# TestBench_rev3.net
KiCad netlist of a schematic drawn in EAGLE
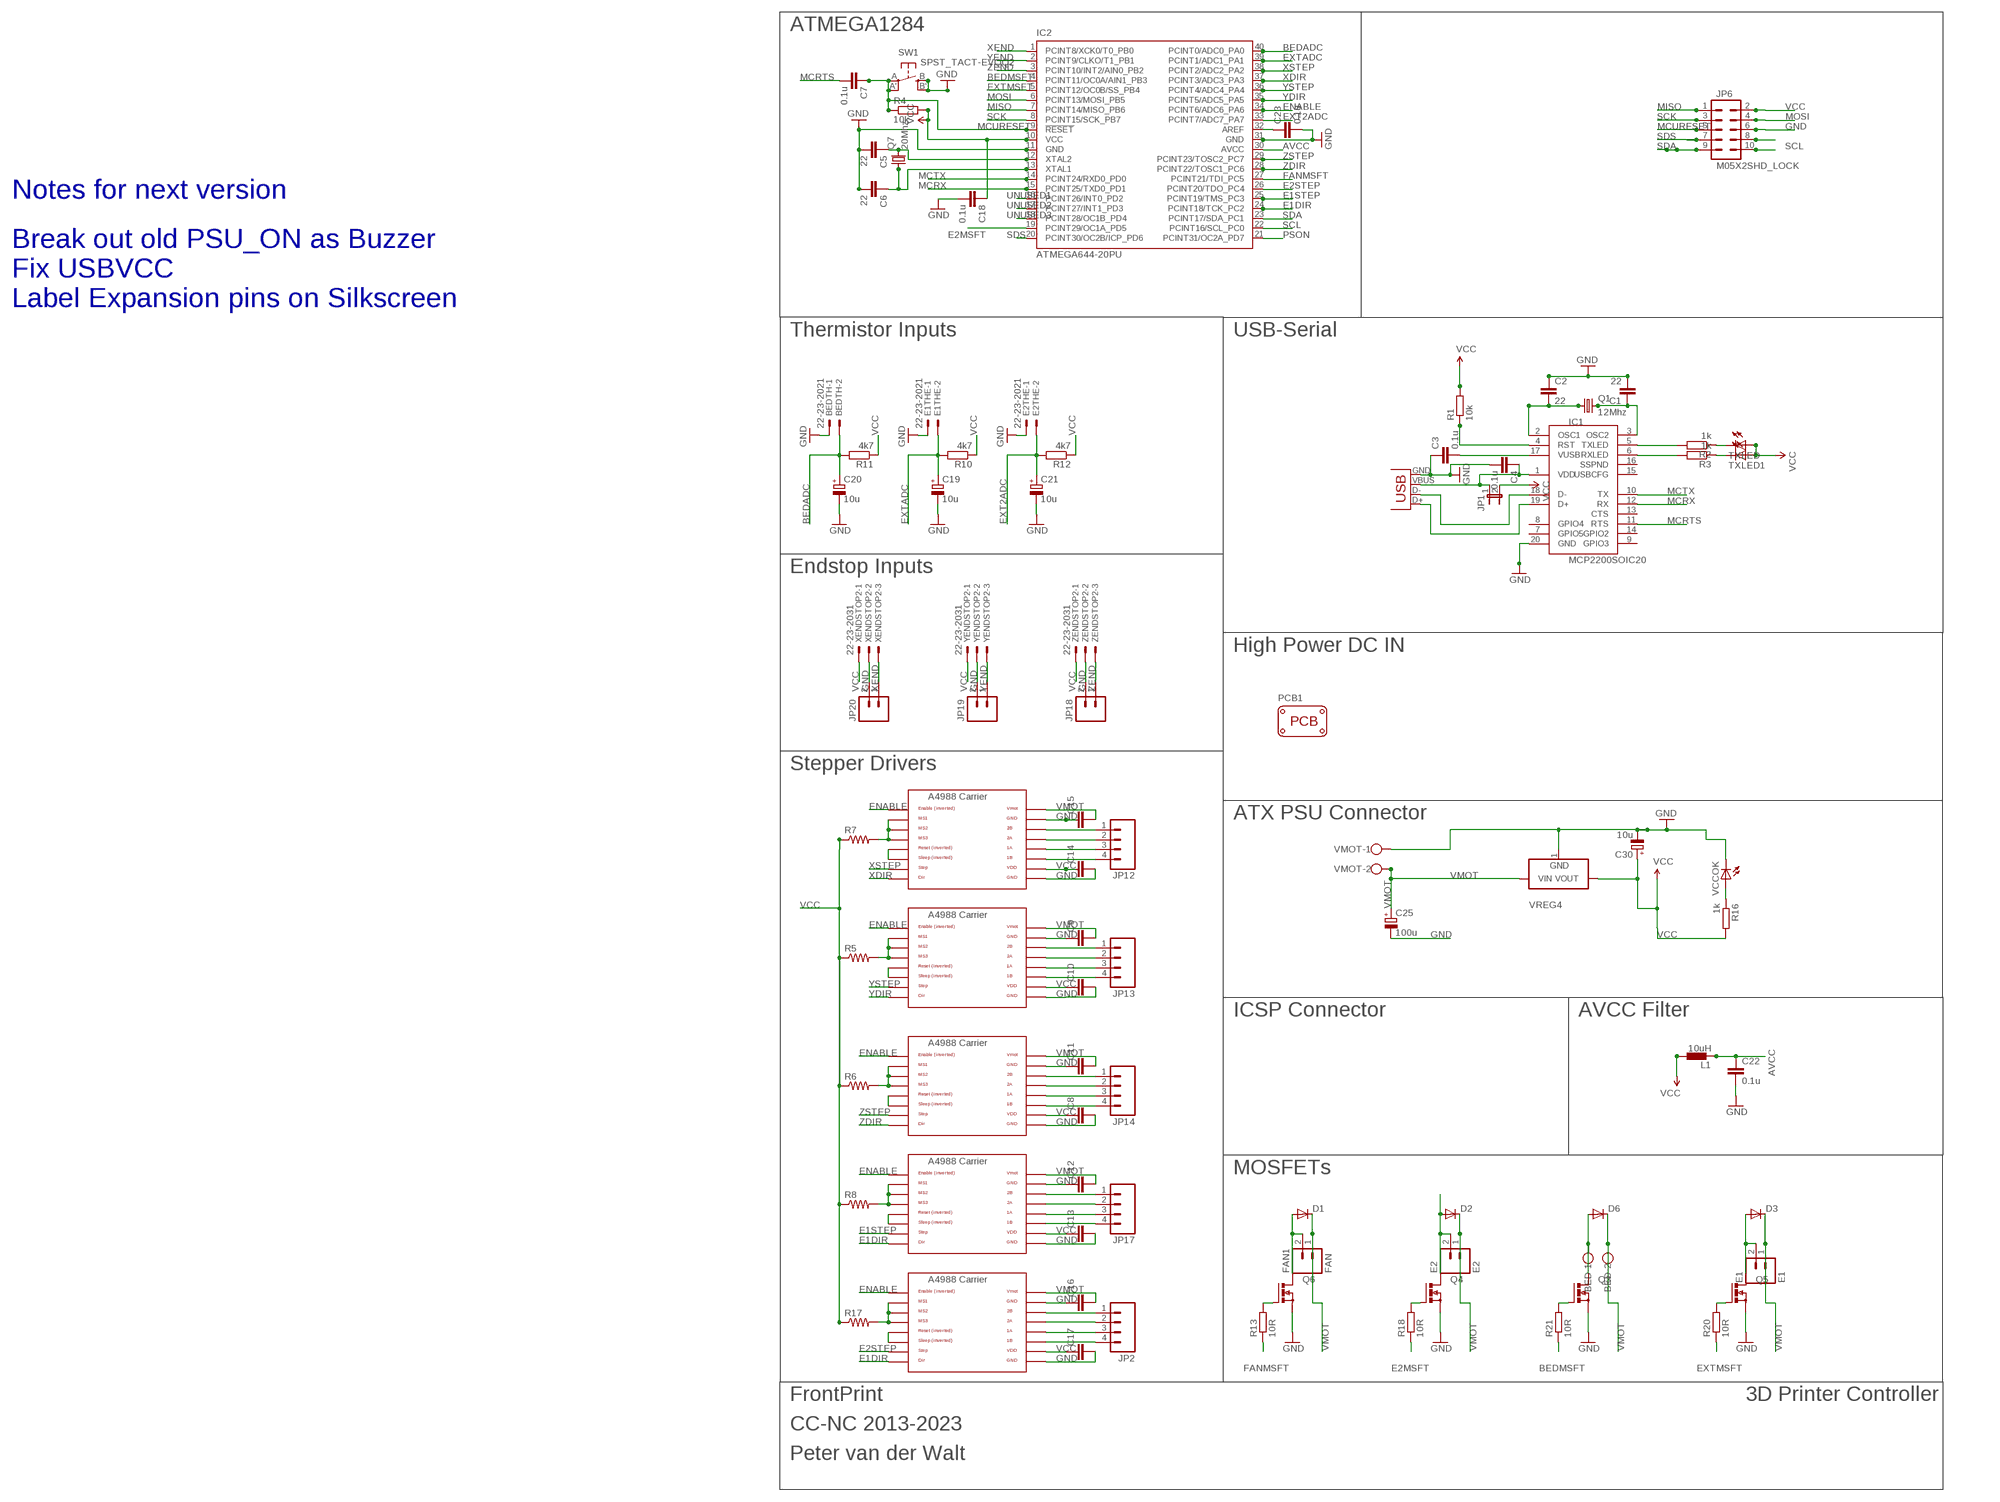
[diagram p0: schematic, sheet 1]

(export (version "E")
  (design (tool "Eeschema 10.0.6"))
  (components
    (comp (ref "BED")
      (value "W237-102")
      (footprint "eagle-import:W237-102")
      (fields (field (name "MPN") "237-102"))
      (libsource (lib "eagle-import") (part "W237-102"))
    )
    (comp (ref "BEDTH")
      (value "22-23-2021")
      (footprint "eagle-import:22-23-2021")
      (fields (field (name "MF") "MOLEX"))
      (libsource (lib "eagle-import") (part "22-23-2021"))
    )
    (comp (ref "C1")
      (value "22")
      (footprint "eagle-import:1206")
      (libsource (lib "eagle-import") (part "CAP1206"))
    )
    (comp (ref "C2")
      (value "22")
      (footprint "eagle-import:1206")
      (libsource (lib "eagle-import") (part "CAP1206"))
    )
    (comp (ref "C3")
      (value "0.1u")
      (footprint "eagle-import:1206")
      (libsource (lib "eagle-import") (part "CAP1206"))
    )
    (comp (ref "C4")
      (value "0.1u")
      (footprint "eagle-import:1206")
      (libsource (lib "eagle-import") (part "CAP1206"))
    )
    (comp (ref "C5")
      (value "22")
      (footprint "eagle-import:1206")
      (libsource (lib "eagle-import") (part "CAP1206"))
    )
    (comp (ref "C6")
      (value "22")
      (footprint "eagle-import:1206")
      (libsource (lib "eagle-import") (part "CAP1206"))
    )
    (comp (ref "C7")
      (value "0.1u")
      (footprint "eagle-import:1206")
      (libsource (lib "eagle-import") (part "CAP1206"))
    )
    (comp (ref "C8")
      (value "CAP1206")
      (footprint "eagle-import:1206")
      (libsource (lib "eagle-import") (part "CAP1206"))
    )
    (comp (ref "C9")
      (value "CAP1206")
      (footprint "eagle-import:1206")
      (libsource (lib "eagle-import") (part "CAP1206"))
    )
    (comp (ref "C10")
      (value "CAP1206")
      (footprint "eagle-import:1206")
      (libsource (lib "eagle-import") (part "CAP1206"))
    )
    (comp (ref "C11")
      (value "CAP1206")
      (footprint "eagle-import:1206")
      (libsource (lib "eagle-import") (part "CAP1206"))
    )
    (comp (ref "C12")
      (value "CAP1206")
      (footprint "eagle-import:1206")
      (libsource (lib "eagle-import") (part "CAP1206"))
    )
    (comp (ref "C13")
      (value "CAP1206")
      (footprint "eagle-import:1206")
      (libsource (lib "eagle-import") (part "CAP1206"))
    )
    (comp (ref "C14")
      (value "CAP1206")
      (footprint "eagle-import:1206")
      (libsource (lib "eagle-import") (part "CAP1206"))
    )
    (comp (ref "C15")
      (value "CAP1206")
      (footprint "eagle-import:1206")
      (libsource (lib "eagle-import") (part "CAP1206"))
    )
    (comp (ref "C16")
      (value "CAP1206")
      (footprint "eagle-import:1206")
      (libsource (lib "eagle-import") (part "CAP1206"))
    )
    (comp (ref "C17")
      (value "CAP1206")
      (footprint "eagle-import:1206")
      (libsource (lib "eagle-import") (part "CAP1206"))
    )
    (comp (ref "C18")
      (value "0.1u")
      (footprint "eagle-import:1206")
      (libsource (lib "eagle-import") (part "CAP1206"))
    )
    (comp (ref "C19")
      (value "10u")
      (footprint "eagle-import:E2,5-5")
      (libsource (lib "eagle-import") (part "CPOL-EUE2.5-5"))
    )
    (comp (ref "C20")
      (value "10u")
      (footprint "eagle-import:E2,5-5")
      (libsource (lib "eagle-import") (part "CPOL-EUE2.5-5"))
    )
    (comp (ref "C21")
      (value "10u")
      (footprint "eagle-import:E2,5-5")
      (libsource (lib "eagle-import") (part "CPOL-EUE2.5-5"))
    )
    (comp (ref "C22")
      (value "0.1u")
      (footprint "eagle-import:1206")
      (libsource (lib "eagle-import") (part "CAP1206"))
    )
    (comp (ref "C23")
      (value "0.1u")
      (footprint "eagle-import:1206")
      (libsource (lib "eagle-import") (part "CAP1206"))
    )
    (comp (ref "C25")
      (value "100u")
      (footprint "eagle-import:E5-8,5")
      (libsource (lib "eagle-import") (part "CPOL-EUE5-8.5"))
    )
    (comp (ref "C30")
      (value "10u")
      (footprint "eagle-import:E2-5")
      (libsource (lib "eagle-import") (part "CPOL-EUE2-5"))
    )
    (comp (ref "D1")
      (value "DIODESMA-ALT")
      (footprint "eagle-import:SMA-DIODE_ALT")
      (libsource (lib "eagle-import") (part "DIODESMA-ALT"))
    )
    (comp (ref "D2")
      (value "DIODESMA-ALT")
      (footprint "eagle-import:SMA-DIODE_ALT")
      (libsource (lib "eagle-import") (part "DIODESMA-ALT"))
    )
    (comp (ref "D3")
      (value "DIODESMA-ALT")
      (footprint "eagle-import:SMA-DIODE_ALT")
      (libsource (lib "eagle-import") (part "DIODESMA-ALT"))
    )
    (comp (ref "D6")
      (value "DIODESMA-ALT")
      (footprint "eagle-import:SMA-DIODE_ALT")
      (libsource (lib "eagle-import") (part "DIODESMA-ALT"))
    )
    (comp (ref "E1")
      (value "E1")
      (footprint "eagle-import:SCREWTERMINAL-3.5MM-2")
      (libsource (lib "eagle-import") (part "M023.5MM"))
    )
    (comp (ref "E1POL")
      (value "POLOLU_A4983CARRIER")
      (footprint "eagle-import:A4988BREAKOUT")
      (libsource (lib "eagle-import") (part "POLOLU_A4983CARRIER"))
    )
    (comp (ref "E1THE")
      (value "22-23-2021")
      (footprint "eagle-import:22-23-2021")
      (fields (field (name "MF") "MOLEX"))
      (libsource (lib "eagle-import") (part "22-23-2021"))
    )
    (comp (ref "E2")
      (value "E2")
      (footprint "eagle-import:SCREWTERMINAL-3.5MM-2")
      (libsource (lib "eagle-import") (part "M023.5MM"))
    )
    (comp (ref "E2POL")
      (value "POLOLU_A4983CARRIER")
      (footprint "eagle-import:A4988BREAKOUT")
      (libsource (lib "eagle-import") (part "POLOLU_A4983CARRIER"))
    )
    (comp (ref "E2THE")
      (value "22-23-2021")
      (footprint "eagle-import:22-23-2021")
      (fields (field (name "MF") "MOLEX"))
      (libsource (lib "eagle-import") (part "22-23-2021"))
    )
    (comp (ref "FAN1")
      (value "FAN")
      (footprint "eagle-import:SCREWTERMINAL-3.5MM-2")
      (libsource (lib "eagle-import") (part "M023.5MM"))
    )
    (comp (ref "IC1")
      (value "MCP2200SOIC20")
      (footprint "eagle-import:SOIC20")
      (libsource (lib "eagle-import") (part "MCP2200SOIC20"))
    )
    (comp (ref "IC2")
      (value "ATMEGA644-20PU")
      (footprint "eagle-import:DIL40")
      (libsource (lib "eagle-import") (part "ATMEGA644-PU20"))
    )
    (comp (ref "JP1")
      (value "JUMPER-2PTH_LOCK")
      (footprint "eagle-import:1X02_LOCK")
      (libsource (lib "eagle-import") (part "JUMPER-2PTH_LOCK"))
    )
    (comp (ref "JP2")
      (value "M04SCREW")
      (footprint "eagle-import:SCREWTERMINAL-3.5MM-4")
      (libsource (lib "eagle-import") (part "M04SCREW"))
    )
    (comp (ref "JP6")
      (value "M05X2SHD_LOCK")
      (footprint "eagle-import:2X5-SHROUDED_LOCK")
      (libsource (lib "eagle-import") (part "M05X2SHD_LOCK"))
    )
    (comp (ref "JP12")
      (value "M04SCREW")
      (footprint "eagle-import:SCREWTERMINAL-3.5MM-4")
      (libsource (lib "eagle-import") (part "M04SCREW"))
    )
    (comp (ref "JP13")
      (value "M04SCREW")
      (footprint "eagle-import:SCREWTERMINAL-3.5MM-4")
      (libsource (lib "eagle-import") (part "M04SCREW"))
    )
    (comp (ref "JP14")
      (value "M04SCREW")
      (footprint "eagle-import:SCREWTERMINAL-3.5MM-4")
      (libsource (lib "eagle-import") (part "M04SCREW"))
    )
    (comp (ref "JP17")
      (value "M04SCREW")
      (footprint "eagle-import:SCREWTERMINAL-3.5MM-4")
      (libsource (lib "eagle-import") (part "M04SCREW"))
    )
    (comp (ref "JP18")
      (value "M023.5MM")
      (footprint "eagle-import:SCREWTERMINAL-3.5MM-2")
      (libsource (lib "eagle-import") (part "M023.5MM"))
    )
    (comp (ref "JP19")
      (value "M023.5MM")
      (footprint "eagle-import:SCREWTERMINAL-3.5MM-2")
      (libsource (lib "eagle-import") (part "M023.5MM"))
    )
    (comp (ref "JP20")
      (value "M023.5MM")
      (footprint "eagle-import:SCREWTERMINAL-3.5MM-2")
      (libsource (lib "eagle-import") (part "M023.5MM"))
    )
    (comp (ref "L1")
      (value "10uH")
      (footprint "eagle-import:BL01RN1A")
      (libsource (lib "eagle-import") (part "BL01RN1A"))
    )
    (comp (ref "PCB1")
      (value "PCB_DP_SQUARE-10X10")
      (footprint "eagle-import:DP100100_V1")
      (libsource (lib "eagle-import") (part "PCB_DP_SQUARE-10X10"))
    )
    (comp (ref "Q1")
      (value "12Mhz")
      (footprint "eagle-import:HC49UP")
      (libsource (lib "eagle-import") (part "CRYSTALHC49UP"))
    )
    (comp (ref "Q3")
      (value "PMOSFET_NTO220BV")
      (footprint "eagle-import:TO220BV")
      (libsource (lib "eagle-import") (part "PMOSFET_NTO220BV"))
    )
    (comp (ref "Q4")
      (value "PMOSFET_NTO220BV")
      (footprint "eagle-import:TO220BV")
      (libsource (lib "eagle-import") (part "PMOSFET_NTO220BV"))
    )
    (comp (ref "Q5")
      (value "PMOSFET_NTO220BV")
      (footprint "eagle-import:TO220BV")
      (libsource (lib "eagle-import") (part "PMOSFET_NTO220BV"))
    )
    (comp (ref "Q6")
      (value "PMOSFET_NTO220BV")
      (footprint "eagle-import:TO220BV")
      (libsource (lib "eagle-import") (part "PMOSFET_NTO220BV"))
    )
    (comp (ref "Q7")
      (value "20Mhz")
      (footprint "eagle-import:HC49UP")
      (fields (field (name "OC_FARNELL") "unknown") (field (name "OC_NEWARK") "unknown"))
      (libsource (lib "eagle-import") (part "CRYSTALHC49UP"))
    )
    (comp (ref "R1")
      (value "10k")
      (footprint "eagle-import:M1206")
      (libsource (lib "eagle-import") (part "R-EU_M1206"))
    )
    (comp (ref "R2")
      (value "1k")
      (footprint "eagle-import:M1206")
      (libsource (lib "eagle-import") (part "R-EU_M1206"))
    )
    (comp (ref "R3")
      (value "1k")
      (footprint "eagle-import:M1206")
      (libsource (lib "eagle-import") (part "R-EU_M1206"))
    )
    (comp (ref "R4")
      (value "10k")
      (footprint "eagle-import:M1206")
      (libsource (lib "eagle-import") (part "R-EU_M1206"))
    )
    (comp (ref "R5")
      (value "RESISTOR1206")
      (footprint "eagle-import:1206")
      (libsource (lib "eagle-import") (part "RESISTOR1206"))
    )
    (comp (ref "R6")
      (value "RESISTOR1206")
      (footprint "eagle-import:1206")
      (libsource (lib "eagle-import") (part "RESISTOR1206"))
    )
    (comp (ref "R7")
      (value "RESISTOR1206")
      (footprint "eagle-import:1206")
      (libsource (lib "eagle-import") (part "RESISTOR1206"))
    )
    (comp (ref "R8")
      (value "RESISTOR1206")
      (footprint "eagle-import:1206")
      (libsource (lib "eagle-import") (part "RESISTOR1206"))
    )
    (comp (ref "R10")
      (value "4k7")
      (footprint "eagle-import:M1206")
      (libsource (lib "eagle-import") (part "R-EU_M1206"))
    )
    (comp (ref "R11")
      (value "4k7")
      (footprint "eagle-import:M1206")
      (libsource (lib "eagle-import") (part "R-EU_M1206"))
    )
    (comp (ref "R12")
      (value "4k7")
      (footprint "eagle-import:M1206")
      (libsource (lib "eagle-import") (part "R-EU_M1206"))
    )
    (comp (ref "R13")
      (value "10R")
      (footprint "eagle-import:M1206")
      (libsource (lib "eagle-import") (part "R-EU_M1206"))
    )
    (comp (ref "R16")
      (value "1k")
      (footprint "eagle-import:M1206")
      (libsource (lib "eagle-import") (part "R-EU_M1206"))
    )
    (comp (ref "R17")
      (value "RESISTOR1206")
      (footprint "eagle-import:1206")
      (libsource (lib "eagle-import") (part "RESISTOR1206"))
    )
    (comp (ref "R18")
      (value "10R")
      (footprint "eagle-import:M1206")
      (libsource (lib "eagle-import") (part "R-EU_M1206"))
    )
    (comp (ref "R20")
      (value "10R")
      (footprint "eagle-import:M1206")
      (libsource (lib "eagle-import") (part "R-EU_M1206"))
    )
    (comp (ref "R21")
      (value "10R")
      (footprint "eagle-import:M1206")
      (libsource (lib "eagle-import") (part "R-EU_M1206"))
    )
    (comp (ref "SW1")
      (value "SPST_TACT-EVQQ2")
      (footprint "eagle-import:EVQ-Q2")
      (libsource (lib "eagle-import") (part "SPST_TACT-EVQQ2"))
    )
    (comp (ref "TXLED")
      (value "LEDSMT1206")
      (footprint "eagle-import:1206")
      (libsource (lib "eagle-import") (part "LEDSMT1206"))
    )
    (comp (ref "TXLED1")
      (value "LEDSMT1206")
      (footprint "eagle-import:1206")
      (libsource (lib "eagle-import") (part "LEDSMT1206"))
    )
    (comp (ref "VCCOK")
      (value "LEDSMT1206")
      (footprint "eagle-import:1206")
      (libsource (lib "eagle-import") (part "LEDSMT1206"))
    )
    (comp (ref "VMOT")
      (value "W237-102")
      (footprint "eagle-import:W237-102")
      (fields
        (field (name "MPN") "237-102")
        (field (name "MPN_1") "237-102")
        (field (name "OC_FARNELL") "unknown")
        (field (name "OC_NEWARK") "70K9898")
      )
      (libsource (lib "eagle-import") (part "W237-102"))
    )
    (comp (ref "VREG4")
      (value "VREG_3PINS-DPAK")
      (footprint "eagle-import:DPAK")
      (libsource (lib "eagle-import") (part "VREG_3PINS-DPAK"))
    )
    (comp (ref "X1")
      (value "USBPTH")
      (footprint "eagle-import:USB-B-PTH")
      (libsource (lib "eagle-import") (part "USBPTH"))
    )
    (comp (ref "XENDSTOP2")
      (value "22-23-2031")
      (footprint "eagle-import:22-23-2031")
      (fields (field (name "MF") "MOLEX"))
      (libsource (lib "eagle-import") (part "22-23-2031"))
    )
    (comp (ref "XPOL")
      (value "POLOLU_A4983CARRIER")
      (footprint "eagle-import:A4988BREAKOUT")
      (libsource (lib "eagle-import") (part "POLOLU_A4983CARRIER"))
    )
    (comp (ref "YENDSTOP2")
      (value "22-23-2031")
      (footprint "eagle-import:22-23-2031")
      (fields (field (name "MF") "MOLEX"))
      (libsource (lib "eagle-import") (part "22-23-2031"))
    )
    (comp (ref "YPOL")
      (value "POLOLU_A4983CARRIER")
      (footprint "eagle-import:A4988BREAKOUT")
      (libsource (lib "eagle-import") (part "POLOLU_A4983CARRIER"))
    )
    (comp (ref "ZENDSTOP2")
      (value "22-23-2031")
      (footprint "eagle-import:22-23-2031")
      (fields (field (name "MF") "MOLEX"))
      (libsource (lib "eagle-import") (part "22-23-2031"))
    )
    (comp (ref "ZPOL")
      (value "POLOLU_A4983CARRIER")
      (footprint "eagle-import:A4988BREAKOUT")
      (libsource (lib "eagle-import") (part "POLOLU_A4983CARRIER"))
    )
  )
  (nets
    (net (code "1") (name "/AVCC") (class "Default")
      (node (ref "C22") (pin "1") (pinfunction "1_1") (pintype "passive"))
      (node (ref "IC2") (pin "30") (pinfunction "AVCC_30") (pintype "power_in"))
      (node (ref "L1") (pin "1") (pinfunction "1_1") (pintype "passive"))
    )
    (net (code "2") (name "/BEDADC") (class "Default")
      (node (ref "BEDTH") (pin "2") (pinfunction "S_2") (pintype "passive"))
      (node (ref "C20") (pin "+") (pinfunction "+_+") (pintype "passive"))
      (node (ref "IC2") (pin "40") (pinfunction "PCINT0/ADC0_PA0_40") (pintype "bidirectional"))
      (node (ref "R11") (pin "2") (pinfunction "2_2") (pintype "passive"))
    )
    (net (code "3") (name "/BEDMSFT") (class "Default")
      (node (ref "IC2") (pin "4") (pinfunction "PCINT11/OC0A/AIN1_PB3_4") (pintype "bidirectional"))
      (node (ref "R21") (pin "1") (pinfunction "1_1") (pintype "passive"))
    )
    (net (code "4") (name "/E1DIR") (class "Default")
      (node (ref "E1POL") (pin "DIR") (pinfunction "DIR_DIR") (pintype "input"))
      (node (ref "E2POL") (pin "DIR") (pinfunction "DIR_DIR") (pintype "input"))
      (node (ref "IC2") (pin "24") (pinfunction "PCINT18/TCK_PC2_24") (pintype "bidirectional"))
    )
    (net (code "5") (name "/E1STEP") (class "Default")
      (node (ref "E1POL") (pin "STEP") (pinfunction "STEP_STEP") (pintype "input"))
      (node (ref "IC2") (pin "25") (pinfunction "PCINT19/TMS_PC3_25") (pintype "bidirectional"))
    )
    (net (code "6") (name "/E2MSFT") (class "Default")
      (node (ref "IC2") (pin "19") (pinfunction "PCINT29/OC1A_PD5_19") (pintype "bidirectional"))
      (node (ref "R18") (pin "1") (pinfunction "1_1") (pintype "passive"))
    )
    (net (code "7") (name "/E2STEP") (class "Default")
      (node (ref "E2POL") (pin "STEP") (pinfunction "STEP_STEP") (pintype "input"))
      (node (ref "IC2") (pin "26") (pinfunction "PCINT20/TDO_PC4_26") (pintype "bidirectional"))
    )
    (net (code "8") (name "/ENABLE") (class "Default")
      (node (ref "E1POL") (pin "EN") (pinfunction "EN_EN") (pintype "input"))
      (node (ref "E2POL") (pin "EN") (pinfunction "EN_EN") (pintype "input"))
      (node (ref "IC2") (pin "34") (pinfunction "PCINT6/ADC6_PA6_34") (pintype "bidirectional"))
      (node (ref "XPOL") (pin "EN") (pinfunction "EN_EN") (pintype "input"))
      (node (ref "YPOL") (pin "EN") (pinfunction "EN_EN") (pintype "input"))
      (node (ref "ZPOL") (pin "EN") (pinfunction "EN_EN") (pintype "input"))
    )
    (net (code "9") (name "/EXT2ADC") (class "Default")
      (node (ref "C21") (pin "+") (pinfunction "+_+") (pintype "passive"))
      (node (ref "E2THE") (pin "2") (pinfunction "S_2") (pintype "passive"))
      (node (ref "IC2") (pin "33") (pinfunction "PCINT7/ADC7_PA7_33") (pintype "bidirectional"))
      (node (ref "R12") (pin "2") (pinfunction "2_2") (pintype "passive"))
    )
    (net (code "10") (name "/EXTADC") (class "Default")
      (node (ref "C19") (pin "+") (pinfunction "+_+") (pintype "passive"))
      (node (ref "E1THE") (pin "2") (pinfunction "S_2") (pintype "passive"))
      (node (ref "IC2") (pin "39") (pinfunction "PCINT1/ADC1_PA1_39") (pintype "bidirectional"))
      (node (ref "R10") (pin "2") (pinfunction "2_2") (pintype "passive"))
    )
    (net (code "11") (name "/EXTMSFT") (class "Default")
      (node (ref "IC2") (pin "5") (pinfunction "PCINT12/OC0B/SS_PB4_5") (pintype "bidirectional"))
      (node (ref "R20") (pin "1") (pinfunction "1_1") (pintype "passive"))
    )
    (net (code "12") (name "/FANMSFT") (class "Default")
      (node (ref "IC2") (pin "27") (pinfunction "PCINT21/TDI_PC5_27") (pintype "bidirectional"))
      (node (ref "R13") (pin "1") (pinfunction "1_1") (pintype "passive"))
    )
    (net (code "13") (name "/MCRTS") (class "Default")
      (node (ref "C7") (pin "2") (pinfunction "2_2") (pintype "passive"))
      (node (ref "IC1") (pin "11") (pinfunction "RTS_11") (pintype "bidirectional"))
    )
    (net (code "14") (name "/MCRX") (class "Default")
      (node (ref "IC1") (pin "12") (pinfunction "RX_12") (pintype "bidirectional"))
      (node (ref "IC2") (pin "15") (pinfunction "PCINT25/TXD0_PD1_15") (pintype "bidirectional"))
    )
    (net (code "15") (name "/MCTX") (class "Default")
      (node (ref "IC1") (pin "10") (pinfunction "TX_10") (pintype "bidirectional"))
      (node (ref "IC2") (pin "14") (pinfunction "PCINT24/RXD0_PD0_14") (pintype "bidirectional"))
    )
    (net (code "16") (name "/MCURESET") (class "Default")
      (node (ref "C7") (pin "1") (pinfunction "1_1") (pintype "passive"))
      (node (ref "IC2") (pin "9") (pinfunction "~{RESET}_9") (pintype "input"))
      (node (ref "JP6") (pin "5") (pinfunction "5_5") (pintype "passive"))
      (node (ref "R4") (pin "1") (pinfunction "1_1") (pintype "passive"))
      (node (ref "SW1") (pin "A") (pinfunction "P_A") (pintype "passive"))
      (node (ref "SW1") (pin "A'") (pinfunction "P1_A'") (pintype "passive"))
    )
    (net (code "17") (name "/MISO") (class "Default")
      (node (ref "IC2") (pin "7") (pinfunction "PCINT14/MISO_PB6_7") (pintype "bidirectional"))
      (node (ref "JP6") (pin "1") (pinfunction "1_1") (pintype "passive"))
    )
    (net (code "18") (name "/MOSI") (class "Default")
      (node (ref "IC2") (pin "6") (pinfunction "PCINT13/MOSI_PB5_6") (pintype "bidirectional"))
      (node (ref "JP6") (pin "4") (pinfunction "4_4") (pintype "passive"))
    )
    (net (code "19") (name "/PSON") (class "Default")
      (node (ref "IC2") (pin "21") (pinfunction "PCINT31/OC2A_PD7_21") (pintype "bidirectional"))
    )
    (net (code "20") (name "/SCK") (class "Default")
      (node (ref "IC2") (pin "8") (pinfunction "PCINT15/SCK_PB7_8") (pintype "bidirectional"))
      (node (ref "JP6") (pin "3") (pinfunction "3_3") (pintype "passive"))
    )
    (net (code "21") (name "/SCL") (class "Default")
      (node (ref "IC2") (pin "22") (pinfunction "PCINT16/SCL_PC0_22") (pintype "bidirectional"))
      (node (ref "JP6") (pin "10") (pinfunction "10_10") (pintype "passive"))
    )
    (net (code "22") (name "/SDA") (class "Default")
      (node (ref "IC2") (pin "23") (pinfunction "PCINT17/SDA_PC1_23") (pintype "bidirectional"))
      (node (ref "JP6") (pin "9") (pinfunction "9_9") (pintype "passive"))
    )
    (net (code "23") (name "/SDS") (class "Default")
      (node (ref "IC2") (pin "20") (pinfunction "PCINT30/OC2B/ICP_PD6_20") (pintype "bidirectional"))
      (node (ref "JP6") (pin "7") (pinfunction "7_7") (pintype "passive"))
    )
    (net (code "24") (name "/UNUSED1") (class "Default")
      (node (ref "IC2") (pin "16") (pinfunction "PCINT26/INT0_PD2_16") (pintype "bidirectional"))
    )
    (net (code "25") (name "/UNUSED2") (class "Default")
      (node (ref "IC2") (pin "17") (pinfunction "PCINT27/INT1_PD3_17") (pintype "bidirectional"))
    )
    (net (code "26") (name "/UNUSED3") (class "Default")
      (node (ref "IC2") (pin "18") (pinfunction "PCINT28/OC1B_PD4_18") (pintype "bidirectional"))
    )
    (net (code "27") (name "/VMOT") (class "Default")
      (node (ref "BED") (pin "2") (pinfunction "KL_2") (pintype "passive"))
      (node (ref "C11") (pin "2") (pinfunction "2_2") (pintype "passive"))
      (node (ref "C12") (pin "2") (pinfunction "2_2") (pintype "passive"))
      (node (ref "C15") (pin "2") (pinfunction "2_2") (pintype "passive"))
      (node (ref "C16") (pin "2") (pinfunction "2_2") (pintype "passive"))
      (node (ref "C25") (pin "+") (pinfunction "+_+") (pintype "passive"))
      (node (ref "C9") (pin "2") (pinfunction "2_2") (pintype "passive"))
      (node (ref "D1") (pin "C") (pinfunction "C_C") (pintype "passive"))
      (node (ref "D2") (pin "C") (pinfunction "C_C") (pintype "passive"))
      (node (ref "D3") (pin "C") (pinfunction "C_C") (pintype "passive"))
      (node (ref "D6") (pin "C") (pinfunction "C_C") (pintype "passive"))
      (node (ref "E1") (pin "1") (pinfunction "1_1") (pintype "passive"))
      (node (ref "E1POL") (pin "VMOT") (pinfunction "VMOT_VMOT") (pintype "power_in"))
      (node (ref "E2") (pin "1") (pinfunction "1_1") (pintype "passive"))
      (node (ref "E2POL") (pin "VMOT") (pinfunction "VMOT_VMOT") (pintype "power_in"))
      (node (ref "FAN1") (pin "1") (pinfunction "1_1") (pintype "passive"))
      (node (ref "VMOT") (pin "2") (pinfunction "KL_2") (pintype "passive"))
      (node (ref "VREG4") (pin "3") (pinfunction "VIN_3") (pintype "bidirectional"))
      (node (ref "XPOL") (pin "VMOT") (pinfunction "VMOT_VMOT") (pintype "power_in"))
      (node (ref "YPOL") (pin "VMOT") (pinfunction "VMOT_VMOT") (pintype "power_in"))
      (node (ref "ZPOL") (pin "VMOT") (pinfunction "VMOT_VMOT") (pintype "power_in"))
    )
    (net (code "28") (name "/XDIR") (class "Default")
      (node (ref "IC2") (pin "37") (pinfunction "PCINT3/ADC3_PA3_37") (pintype "bidirectional"))
      (node (ref "XPOL") (pin "DIR") (pinfunction "DIR_DIR") (pintype "input"))
    )
    (net (code "29") (name "/XEND") (class "Default")
      (node (ref "IC2") (pin "1") (pinfunction "PCINT8/XCK0/T0_PB0_1") (pintype "bidirectional"))
      (node (ref "JP20") (pin "1") (pinfunction "1_1") (pintype "passive"))
      (node (ref "XENDSTOP2") (pin "3") (pinfunction "S_3") (pintype "passive"))
    )
    (net (code "30") (name "/XSTEP") (class "Default")
      (node (ref "IC2") (pin "38") (pinfunction "PCINT2/ADC2_PA2_38") (pintype "bidirectional"))
      (node (ref "XPOL") (pin "STEP") (pinfunction "STEP_STEP") (pintype "input"))
    )
    (net (code "31") (name "/YDIR") (class "Default")
      (node (ref "IC2") (pin "35") (pinfunction "PCINT5/ADC5_PA5_35") (pintype "bidirectional"))
      (node (ref "YPOL") (pin "DIR") (pinfunction "DIR_DIR") (pintype "input"))
    )
    (net (code "32") (name "/YEND") (class "Default")
      (node (ref "IC2") (pin "2") (pinfunction "PCINT9/CLKO/T1_PB1_2") (pintype "bidirectional"))
      (node (ref "JP19") (pin "1") (pinfunction "1_1") (pintype "passive"))
      (node (ref "YENDSTOP2") (pin "3") (pinfunction "S_3") (pintype "passive"))
    )
    (net (code "33") (name "/YSTEP") (class "Default")
      (node (ref "IC2") (pin "36") (pinfunction "PCINT4/ADC4_PA4_36") (pintype "bidirectional"))
      (node (ref "YPOL") (pin "STEP") (pinfunction "STEP_STEP") (pintype "input"))
    )
    (net (code "34") (name "/ZDIR") (class "Default")
      (node (ref "IC2") (pin "28") (pinfunction "PCINT22/TOSC1_PC6_28") (pintype "bidirectional"))
      (node (ref "ZPOL") (pin "DIR") (pinfunction "DIR_DIR") (pintype "input"))
    )
    (net (code "35") (name "/ZEND") (class "Default")
      (node (ref "IC2") (pin "3") (pinfunction "PCINT10/INT2/AIN0_PB2_3") (pintype "bidirectional"))
      (node (ref "JP18") (pin "1") (pinfunction "1_1") (pintype "passive"))
      (node (ref "ZENDSTOP2") (pin "3") (pinfunction "S_3") (pintype "passive"))
    )
    (net (code "36") (name "/ZSTEP") (class "Default")
      (node (ref "IC2") (pin "29") (pinfunction "PCINT23/TOSC2_PC7_29") (pintype "bidirectional"))
      (node (ref "ZPOL") (pin "STEP") (pinfunction "STEP_STEP") (pintype "input"))
    )
    (net (code "37") (name "GND") (class "Default")
      (node (ref "BEDTH") (pin "1") (pinfunction "S_1") (pintype "passive"))
      (node (ref "C1") (pin "2") (pinfunction "2_2") (pintype "passive"))
      (node (ref "C10") (pin "2") (pinfunction "2_2") (pintype "passive"))
      (node (ref "C11") (pin "1") (pinfunction "1_1") (pintype "passive"))
      (node (ref "C12") (pin "1") (pinfunction "1_1") (pintype "passive"))
      (node (ref "C13") (pin "2") (pinfunction "2_2") (pintype "passive"))
      (node (ref "C14") (pin "2") (pinfunction "2_2") (pintype "passive"))
      (node (ref "C15") (pin "1") (pinfunction "1_1") (pintype "passive"))
      (node (ref "C16") (pin "1") (pinfunction "1_1") (pintype "passive"))
      (node (ref "C17") (pin "2") (pinfunction "2_2") (pintype "passive"))
      (node (ref "C18") (pin "2") (pinfunction "2_2") (pintype "passive"))
      (node (ref "C19") (pin "-") (pinfunction "-_-") (pintype "passive"))
      (node (ref "C2") (pin "1") (pinfunction "1_1") (pintype "passive"))
      (node (ref "C20") (pin "-") (pinfunction "-_-") (pintype "passive"))
      (node (ref "C21") (pin "-") (pinfunction "-_-") (pintype "passive"))
      (node (ref "C22") (pin "2") (pinfunction "2_2") (pintype "passive"))
      (node (ref "C23") (pin "2") (pinfunction "2_2") (pintype "passive"))
      (node (ref "C25") (pin "-") (pinfunction "-_-") (pintype "passive"))
      (node (ref "C3") (pin "1") (pinfunction "1_1") (pintype "passive"))
      (node (ref "C30") (pin "-") (pinfunction "-_-") (pintype "passive"))
      (node (ref "C4") (pin "2") (pinfunction "2_2") (pintype "passive"))
      (node (ref "C5") (pin "2") (pinfunction "2_2") (pintype "passive"))
      (node (ref "C6") (pin "2") (pinfunction "2_2") (pintype "passive"))
      (node (ref "C8") (pin "2") (pinfunction "2_2") (pintype "passive"))
      (node (ref "C9") (pin "1") (pinfunction "1_1") (pintype "passive"))
      (node (ref "E1POL") (pin "GND") (pinfunction "GND_GND") (pintype "power_in"))
      (node (ref "E1POL") (pin "GND@0") (pinfunction "GND_GND@0") (pintype "power_in"))
      (node (ref "E1THE") (pin "1") (pinfunction "S_1") (pintype "passive"))
      (node (ref "E2POL") (pin "GND") (pinfunction "GND_GND") (pintype "power_in"))
      (node (ref "E2POL") (pin "GND@0") (pinfunction "GND_GND@0") (pintype "power_in"))
      (node (ref "E2THE") (pin "1") (pinfunction "S_1") (pintype "passive"))
      (node (ref "IC1") (pin "20") (pinfunction "GND_20") (pintype "bidirectional"))
      (node (ref "IC2") (pin "11") (pinfunction "GND_11") (pintype "power_in"))
      (node (ref "IC2") (pin "31") (pinfunction "GND_31") (pintype "power_in"))
      (node (ref "JP18") (pin "2") (pinfunction "2_2") (pintype "passive"))
      (node (ref "JP19") (pin "2") (pinfunction "2_2") (pintype "passive"))
      (node (ref "JP20") (pin "2") (pinfunction "2_2") (pintype "passive"))
      (node (ref "JP6") (pin "6") (pinfunction "6_6") (pintype "passive"))
      (node (ref "Q3") (pin "S") (pinfunction "S_S") (pintype "passive"))
      (node (ref "Q4") (pin "S") (pinfunction "S_S") (pintype "passive"))
      (node (ref "Q5") (pin "S") (pinfunction "S_S") (pintype "passive"))
      (node (ref "Q6") (pin "S") (pinfunction "S_S") (pintype "passive"))
      (node (ref "SW1") (pin "B") (pinfunction "S_B") (pintype "passive"))
      (node (ref "SW1") (pin "B'") (pinfunction "S1_B'") (pintype "passive"))
      (node (ref "VCCOK") (pin "C") (pinfunction "C_C") (pintype "passive"))
      (node (ref "VMOT") (pin "1") (pinfunction "KL_1") (pintype "passive"))
      (node (ref "VREG4") (pin "1") (pinfunction "GND_1") (pintype "bidirectional"))
      (node (ref "X1") (pin "GND") (pinfunction "GND_GND") (pintype "bidirectional"))
      (node (ref "XENDSTOP2") (pin "2") (pinfunction "S_2") (pintype "passive"))
      (node (ref "XPOL") (pin "GND") (pinfunction "GND_GND") (pintype "power_in"))
      (node (ref "XPOL") (pin "GND@0") (pinfunction "GND_GND@0") (pintype "power_in"))
      (node (ref "YENDSTOP2") (pin "2") (pinfunction "S_2") (pintype "passive"))
      (node (ref "YPOL") (pin "GND") (pinfunction "GND_GND") (pintype "power_in"))
      (node (ref "YPOL") (pin "GND@0") (pinfunction "GND_GND@0") (pintype "power_in"))
      (node (ref "ZENDSTOP2") (pin "2") (pinfunction "S_2") (pintype "passive"))
      (node (ref "ZPOL") (pin "GND") (pinfunction "GND_GND") (pintype "power_in"))
      (node (ref "ZPOL") (pin "GND@0") (pinfunction "GND_GND@0") (pintype "power_in"))
    )
    (net (code "38") (name "Net-(BEDA-KL)") (class "Default")
      (node (ref "BED") (pin "1") (pinfunction "KL_1") (pintype "passive"))
      (node (ref "D6") (pin "A") (pinfunction "A_A") (pintype "passive"))
      (node (ref "Q3") (pin "D") (pinfunction "D_D") (pintype "passive"))
    )
    (net (code "39") (name "Net-(D1-PadA)") (class "Default")
      (node (ref "D1") (pin "A") (pinfunction "A_A") (pintype "passive"))
      (node (ref "FAN1") (pin "2") (pinfunction "2_2") (pintype "passive"))
      (node (ref "Q6") (pin "D") (pinfunction "D_D") (pintype "passive"))
    )
    (net (code "40") (name "Net-(D2-PadA)") (class "Default")
      (node (ref "D2") (pin "A") (pinfunction "A_A") (pintype "passive"))
      (node (ref "E2") (pin "2") (pinfunction "2_2") (pintype "passive"))
      (node (ref "Q4") (pin "D") (pinfunction "D_D") (pintype "passive"))
    )
    (net (code "41") (name "Net-(D3-PadA)") (class "Default")
      (node (ref "D3") (pin "A") (pinfunction "A_A") (pintype "passive"))
      (node (ref "E1") (pin "2") (pinfunction "2_2") (pintype "passive"))
      (node (ref "Q5") (pin "D") (pinfunction "D_D") (pintype "passive"))
    )
    (net (code "42") (name "Net-(E1POL-Pad1A)") (class "Default")
      (node (ref "E1POL") (pin "1A") (pinfunction "1A_1A") (pintype "output"))
      (node (ref "JP17") (pin "3") (pinfunction "3_3") (pintype "passive"))
    )
    (net (code "43") (name "Net-(E1POL-Pad1B)") (class "Default")
      (node (ref "E1POL") (pin "1B") (pinfunction "1B_1B") (pintype "output"))
      (node (ref "JP17") (pin "4") (pinfunction "4_4") (pintype "passive"))
    )
    (net (code "44") (name "Net-(E1POL-Pad2A)") (class "Default")
      (node (ref "E1POL") (pin "2A") (pinfunction "2A_2A") (pintype "output"))
      (node (ref "JP17") (pin "2") (pinfunction "2_2") (pintype "passive"))
    )
    (net (code "45") (name "Net-(E1POL-Pad2B)") (class "Default")
      (node (ref "E1POL") (pin "2B") (pinfunction "2B_2B") (pintype "output"))
      (node (ref "JP17") (pin "1") (pinfunction "1_1") (pintype "passive"))
    )
    (net (code "46") (name "Net-(E1POL-PadMS1)") (class "Default")
      (node (ref "E1POL") (pin "MS1") (pinfunction "MS1_MS1") (pintype "input"))
      (node (ref "E1POL") (pin "MS2") (pinfunction "MS2_MS2") (pintype "input"))
      (node (ref "E1POL") (pin "MS3") (pinfunction "MS3_MS3") (pintype "input"))
      (node (ref "R8") (pin "2") (pinfunction "2_2") (pintype "passive"))
    )
    (net (code "47") (name "Net-(E1POL-SLEEP)") (class "Default")
      (node (ref "E1POL") (pin "RST") (pinfunction "RST_RST") (pintype "input"))
      (node (ref "E1POL") (pin "SLP") (pinfunction "SLEEP_SLP") (pintype "input"))
    )
    (net (code "48") (name "Net-(E2POL-Pad1A)") (class "Default")
      (node (ref "E2POL") (pin "1A") (pinfunction "1A_1A") (pintype "output"))
      (node (ref "JP2") (pin "3") (pinfunction "3_3") (pintype "passive"))
    )
    (net (code "49") (name "Net-(E2POL-Pad1B)") (class "Default")
      (node (ref "E2POL") (pin "1B") (pinfunction "1B_1B") (pintype "output"))
      (node (ref "JP2") (pin "4") (pinfunction "4_4") (pintype "passive"))
    )
    (net (code "50") (name "Net-(E2POL-Pad2A)") (class "Default")
      (node (ref "E2POL") (pin "2A") (pinfunction "2A_2A") (pintype "output"))
      (node (ref "JP2") (pin "2") (pinfunction "2_2") (pintype "passive"))
    )
    (net (code "51") (name "Net-(E2POL-Pad2B)") (class "Default")
      (node (ref "E2POL") (pin "2B") (pinfunction "2B_2B") (pintype "output"))
      (node (ref "JP2") (pin "1") (pinfunction "1_1") (pintype "passive"))
    )
    (net (code "52") (name "Net-(E2POL-PadMS1)") (class "Default")
      (node (ref "E2POL") (pin "MS1") (pinfunction "MS1_MS1") (pintype "input"))
      (node (ref "E2POL") (pin "MS2") (pinfunction "MS2_MS2") (pintype "input"))
      (node (ref "E2POL") (pin "MS3") (pinfunction "MS3_MS3") (pintype "input"))
      (node (ref "R17") (pin "2") (pinfunction "2_2") (pintype "passive"))
    )
    (net (code "53") (name "Net-(E2POL-SLEEP)") (class "Default")
      (node (ref "E2POL") (pin "RST") (pinfunction "RST_RST") (pintype "input"))
      (node (ref "E2POL") (pin "SLP") (pinfunction "SLEEP_SLP") (pintype "input"))
    )
    (net (code "54") (name "Net-(IC1-D+)") (class "Default")
      (node (ref "IC1") (pin "19") (pinfunction "D+_19") (pintype "bidirectional"))
      (node (ref "X1") (pin "D+") (pinfunction "D+_D+") (pintype "bidirectional"))
    )
    (net (code "55") (name "Net-(IC1-D-)") (class "Default")
      (node (ref "IC1") (pin "18") (pinfunction "D-_18") (pintype "bidirectional"))
      (node (ref "X1") (pin "D-") (pinfunction "D-_D-") (pintype "bidirectional"))
    )
    (net (code "56") (name "Net-(IC1-OSC1)") (class "Default")
      (node (ref "C2") (pin "2") (pinfunction "2_2") (pintype "passive"))
      (node (ref "IC1") (pin "2") (pinfunction "OSC1_2") (pintype "bidirectional"))
      (node (ref "Q1") (pin "1") (pinfunction "1_1") (pintype "passive"))
    )
    (net (code "57") (name "Net-(IC1-OSC2)") (class "Default")
      (node (ref "C1") (pin "1") (pinfunction "1_1") (pintype "passive"))
      (node (ref "IC1") (pin "3") (pinfunction "OSC2_3") (pintype "bidirectional"))
      (node (ref "Q1") (pin "2") (pinfunction "2_2") (pintype "passive"))
    )
    (net (code "58") (name "Net-(IC1-RST)") (class "Default")
      (node (ref "IC1") (pin "4") (pinfunction "RST_4") (pintype "bidirectional"))
      (node (ref "R1") (pin "1") (pinfunction "1_1") (pintype "passive"))
    )
    (net (code "59") (name "Net-(IC1-RXLED)") (class "Default")
      (node (ref "IC1") (pin "6") (pinfunction "RXLED_6") (pintype "bidirectional"))
      (node (ref "R3") (pin "2") (pinfunction "2_2") (pintype "passive"))
    )
    (net (code "60") (name "Net-(IC1-TXLED)") (class "Default")
      (node (ref "IC1") (pin "5") (pinfunction "TXLED_5") (pintype "bidirectional"))
      (node (ref "R2") (pin "2") (pinfunction "2_2") (pintype "passive"))
    )
    (net (code "61") (name "Net-(IC1-VDD)") (class "Default")
      (node (ref "C4") (pin "1") (pinfunction "1_1") (pintype "passive"))
      (node (ref "IC1") (pin "1") (pinfunction "VDD_1") (pintype "bidirectional"))
      (node (ref "JP1") (pin "1") (pinfunction "1_1") (pintype "passive"))
      (node (ref "X1") (pin "VBUS") (pinfunction "VBUS_VBUS") (pintype "bidirectional"))
    )
    (net (code "62") (name "Net-(IC1-VUSB)") (class "Default")
      (node (ref "C3") (pin "2") (pinfunction "2_2") (pintype "passive"))
      (node (ref "IC1") (pin "17") (pinfunction "VUSB_17") (pintype "bidirectional"))
    )
    (net (code "63") (name "Net-(IC2-AREF)") (class "Default")
      (node (ref "C23") (pin "1") (pinfunction "1_1") (pintype "passive"))
      (node (ref "IC2") (pin "32") (pinfunction "AREF_32") (pintype "passive"))
    )
    (net (code "64") (name "Net-(IC2-XTAL1)") (class "Default")
      (node (ref "C6") (pin "1") (pinfunction "1_1") (pintype "passive"))
      (node (ref "IC2") (pin "13") (pinfunction "XTAL1_13") (pintype "input"))
      (node (ref "Q7") (pin "1") (pinfunction "1_1") (pintype "passive"))
    )
    (net (code "65") (name "Net-(IC2-XTAL2)") (class "Default")
      (node (ref "C5") (pin "1") (pinfunction "1_1") (pintype "passive"))
      (node (ref "IC2") (pin "12") (pinfunction "XTAL2_12") (pintype "output"))
      (node (ref "Q7") (pin "2") (pinfunction "2_2") (pintype "passive"))
    )
    (net (code "66") (name "Net-(JP12-Pad1)") (class "Default")
      (node (ref "JP12") (pin "1") (pinfunction "1_1") (pintype "passive"))
      (node (ref "XPOL") (pin "2B") (pinfunction "2B_2B") (pintype "output"))
    )
    (net (code "67") (name "Net-(JP12-Pad2)") (class "Default")
      (node (ref "JP12") (pin "2") (pinfunction "2_2") (pintype "passive"))
      (node (ref "XPOL") (pin "2A") (pinfunction "2A_2A") (pintype "output"))
    )
    (net (code "68") (name "Net-(JP12-Pad3)") (class "Default")
      (node (ref "JP12") (pin "3") (pinfunction "3_3") (pintype "passive"))
      (node (ref "XPOL") (pin "1A") (pinfunction "1A_1A") (pintype "output"))
    )
    (net (code "69") (name "Net-(JP12-Pad4)") (class "Default")
      (node (ref "JP12") (pin "4") (pinfunction "4_4") (pintype "passive"))
      (node (ref "XPOL") (pin "1B") (pinfunction "1B_1B") (pintype "output"))
    )
    (net (code "70") (name "Net-(JP13-Pad1)") (class "Default")
      (node (ref "JP13") (pin "1") (pinfunction "1_1") (pintype "passive"))
      (node (ref "YPOL") (pin "2B") (pinfunction "2B_2B") (pintype "output"))
    )
    (net (code "71") (name "Net-(JP13-Pad2)") (class "Default")
      (node (ref "JP13") (pin "2") (pinfunction "2_2") (pintype "passive"))
      (node (ref "YPOL") (pin "2A") (pinfunction "2A_2A") (pintype "output"))
    )
    (net (code "72") (name "Net-(JP13-Pad3)") (class "Default")
      (node (ref "JP13") (pin "3") (pinfunction "3_3") (pintype "passive"))
      (node (ref "YPOL") (pin "1A") (pinfunction "1A_1A") (pintype "output"))
    )
    (net (code "73") (name "Net-(JP13-Pad4)") (class "Default")
      (node (ref "JP13") (pin "4") (pinfunction "4_4") (pintype "passive"))
      (node (ref "YPOL") (pin "1B") (pinfunction "1B_1B") (pintype "output"))
    )
    (net (code "74") (name "Net-(JP14-Pad1)") (class "Default")
      (node (ref "JP14") (pin "1") (pinfunction "1_1") (pintype "passive"))
      (node (ref "ZPOL") (pin "2B") (pinfunction "2B_2B") (pintype "output"))
    )
    (net (code "75") (name "Net-(JP14-Pad2)") (class "Default")
      (node (ref "JP14") (pin "2") (pinfunction "2_2") (pintype "passive"))
      (node (ref "ZPOL") (pin "2A") (pinfunction "2A_2A") (pintype "output"))
    )
    (net (code "76") (name "Net-(JP14-Pad3)") (class "Default")
      (node (ref "JP14") (pin "3") (pinfunction "3_3") (pintype "passive"))
      (node (ref "ZPOL") (pin "1A") (pinfunction "1A_1A") (pintype "output"))
    )
    (net (code "77") (name "Net-(JP14-Pad4)") (class "Default")
      (node (ref "JP14") (pin "4") (pinfunction "4_4") (pintype "passive"))
      (node (ref "ZPOL") (pin "1B") (pinfunction "1B_1B") (pintype "output"))
    )
    (net (code "78") (name "Net-(Q3-PadG)") (class "Default")
      (node (ref "Q3") (pin "G") (pinfunction "G_G") (pintype "passive"))
      (node (ref "R21") (pin "2") (pinfunction "2_2") (pintype "passive"))
    )
    (net (code "79") (name "Net-(Q4-PadG)") (class "Default")
      (node (ref "Q4") (pin "G") (pinfunction "G_G") (pintype "passive"))
      (node (ref "R18") (pin "2") (pinfunction "2_2") (pintype "passive"))
    )
    (net (code "80") (name "Net-(Q5-PadG)") (class "Default")
      (node (ref "Q5") (pin "G") (pinfunction "G_G") (pintype "passive"))
      (node (ref "R20") (pin "2") (pinfunction "2_2") (pintype "passive"))
    )
    (net (code "81") (name "Net-(Q6-PadG)") (class "Default")
      (node (ref "Q6") (pin "G") (pinfunction "G_G") (pintype "passive"))
      (node (ref "R13") (pin "2") (pinfunction "2_2") (pintype "passive"))
    )
    (net (code "82") (name "Net-(R2-Pad1)") (class "Default")
      (node (ref "R2") (pin "1") (pinfunction "1_1") (pintype "passive"))
      (node (ref "TXLED") (pin "C") (pinfunction "C_C") (pintype "passive"))
    )
    (net (code "83") (name "Net-(R3-Pad1)") (class "Default")
      (node (ref "R3") (pin "1") (pinfunction "1_1") (pintype "passive"))
      (node (ref "TXLED1") (pin "C") (pinfunction "C_C") (pintype "passive"))
    )
    (net (code "84") (name "Net-(R5-Pad2)") (class "Default")
      (node (ref "R5") (pin "2") (pinfunction "2_2") (pintype "passive"))
      (node (ref "YPOL") (pin "MS1") (pinfunction "MS1_MS1") (pintype "input"))
      (node (ref "YPOL") (pin "MS2") (pinfunction "MS2_MS2") (pintype "input"))
      (node (ref "YPOL") (pin "MS3") (pinfunction "MS3_MS3") (pintype "input"))
    )
    (net (code "85") (name "Net-(R6-Pad2)") (class "Default")
      (node (ref "R6") (pin "2") (pinfunction "2_2") (pintype "passive"))
      (node (ref "ZPOL") (pin "MS1") (pinfunction "MS1_MS1") (pintype "input"))
      (node (ref "ZPOL") (pin "MS2") (pinfunction "MS2_MS2") (pintype "input"))
      (node (ref "ZPOL") (pin "MS3") (pinfunction "MS3_MS3") (pintype "input"))
    )
    (net (code "86") (name "Net-(R7-Pad2)") (class "Default")
      (node (ref "R7") (pin "2") (pinfunction "2_2") (pintype "passive"))
      (node (ref "XPOL") (pin "MS1") (pinfunction "MS1_MS1") (pintype "input"))
      (node (ref "XPOL") (pin "MS2") (pinfunction "MS2_MS2") (pintype "input"))
      (node (ref "XPOL") (pin "MS3") (pinfunction "MS3_MS3") (pintype "input"))
    )
    (net (code "87") (name "Net-(R16-Pad1)") (class "Default")
      (node (ref "R16") (pin "1") (pinfunction "1_1") (pintype "passive"))
      (node (ref "VCCOK") (pin "A") (pinfunction "A_A") (pintype "passive"))
    )
    (net (code "88") (name "Net-(XPOL-SLEEP)") (class "Default")
      (node (ref "XPOL") (pin "RST") (pinfunction "RST_RST") (pintype "input"))
      (node (ref "XPOL") (pin "SLP") (pinfunction "SLEEP_SLP") (pintype "input"))
    )
    (net (code "89") (name "Net-(YPOL-SLEEP)") (class "Default")
      (node (ref "YPOL") (pin "RST") (pinfunction "RST_RST") (pintype "input"))
      (node (ref "YPOL") (pin "SLP") (pinfunction "SLEEP_SLP") (pintype "input"))
    )
    (net (code "90") (name "Net-(ZPOL-SLEEP)") (class "Default")
      (node (ref "ZPOL") (pin "RST") (pinfunction "RST_RST") (pintype "input"))
      (node (ref "ZPOL") (pin "SLP") (pinfunction "SLEEP_SLP") (pintype "input"))
    )
    (net (code "91") (name "VCC") (class "Default")
      (node (ref "C10") (pin "1") (pinfunction "1_1") (pintype "passive"))
      (node (ref "C13") (pin "1") (pinfunction "1_1") (pintype "passive"))
      (node (ref "C14") (pin "1") (pinfunction "1_1") (pintype "passive"))
      (node (ref "C17") (pin "1") (pinfunction "1_1") (pintype "passive"))
      (node (ref "C18") (pin "1") (pinfunction "1_1") (pintype "passive"))
      (node (ref "C30") (pin "+") (pinfunction "+_+") (pintype "passive"))
      (node (ref "C8") (pin "1") (pinfunction "1_1") (pintype "passive"))
      (node (ref "E1POL") (pin "VDD") (pinfunction "VDD_VDD") (pintype "power_in"))
      (node (ref "E2POL") (pin "VDD") (pinfunction "VDD_VDD") (pintype "power_in"))
      (node (ref "IC2") (pin "10") (pinfunction "VCC_10") (pintype "power_in"))
      (node (ref "JP1") (pin "2") (pinfunction "2_2") (pintype "passive"))
      (node (ref "JP6") (pin "2") (pinfunction "2_2") (pintype "passive"))
      (node (ref "L1") (pin "2") (pinfunction "2_2") (pintype "passive"))
      (node (ref "R1") (pin "2") (pinfunction "2_2") (pintype "passive"))
      (node (ref "R10") (pin "1") (pinfunction "1_1") (pintype "passive"))
      (node (ref "R11") (pin "1") (pinfunction "1_1") (pintype "passive"))
      (node (ref "R12") (pin "1") (pinfunction "1_1") (pintype "passive"))
      (node (ref "R16") (pin "2") (pinfunction "2_2") (pintype "passive"))
      (node (ref "R17") (pin "1") (pinfunction "1_1") (pintype "passive"))
      (node (ref "R4") (pin "2") (pinfunction "2_2") (pintype "passive"))
      (node (ref "R5") (pin "1") (pinfunction "1_1") (pintype "passive"))
      (node (ref "R6") (pin "1") (pinfunction "1_1") (pintype "passive"))
      (node (ref "R7") (pin "1") (pinfunction "1_1") (pintype "passive"))
      (node (ref "R8") (pin "1") (pinfunction "1_1") (pintype "passive"))
      (node (ref "TXLED") (pin "A") (pinfunction "A_A") (pintype "passive"))
      (node (ref "TXLED1") (pin "A") (pinfunction "A_A") (pintype "passive"))
      (node (ref "VREG4") (pin "2") (pinfunction "VOUT_2") (pintype "bidirectional"))
      (node (ref "XENDSTOP2") (pin "1") (pinfunction "S_1") (pintype "passive"))
      (node (ref "XPOL") (pin "VDD") (pinfunction "VDD_VDD") (pintype "power_in"))
      (node (ref "YENDSTOP2") (pin "1") (pinfunction "S_1") (pintype "passive"))
      (node (ref "YPOL") (pin "VDD") (pinfunction "VDD_VDD") (pintype "power_in"))
      (node (ref "ZENDSTOP2") (pin "1") (pinfunction "S_1") (pintype "passive"))
      (node (ref "ZPOL") (pin "VDD") (pinfunction "VDD_VDD") (pintype "power_in"))
    )
    (net (code "92") (name "unconnected-(IC1-CTS-Pad13)") (class "Default")
      (node (ref "IC1") (pin "13") (pinfunction "CTS_13") (pintype "bidirectional"))
    )
    (net (code "93") (name "unconnected-(IC1-GPIO2-Pad14)") (class "Default")
      (node (ref "IC1") (pin "14") (pinfunction "GPIO2_14") (pintype "bidirectional"))
    )
    (net (code "94") (name "unconnected-(IC1-GPIO3-Pad9)") (class "Default")
      (node (ref "IC1") (pin "9") (pinfunction "GPIO3_9") (pintype "bidirectional"))
    )
    (net (code "95") (name "unconnected-(IC1-GPIO4-Pad8)") (class "Default")
      (node (ref "IC1") (pin "8") (pinfunction "GPIO4_8") (pintype "bidirectional"))
    )
    (net (code "96") (name "unconnected-(IC1-GPIO5-Pad7)") (class "Default")
      (node (ref "IC1") (pin "7") (pinfunction "GPIO5_7") (pintype "bidirectional"))
    )
    (net (code "97") (name "unconnected-(IC1-SSPND-Pad16)") (class "Default")
      (node (ref "IC1") (pin "16") (pinfunction "SSPND_16") (pintype "bidirectional"))
    )
    (net (code "98") (name "unconnected-(IC1-USBCFG-Pad15)") (class "Default")
      (node (ref "IC1") (pin "15") (pinfunction "USBCFG_15") (pintype "bidirectional"))
    )
    (net (code "99") (name "unconnected-(JP6-Pad8)") (class "Default")
      (node (ref "JP6") (pin "8") (pinfunction "8_8") (pintype "passive"))
    )
  )
)
